# C30_Pocket_Console.net
KiCad netlist of a schematic drawn in EAGLE
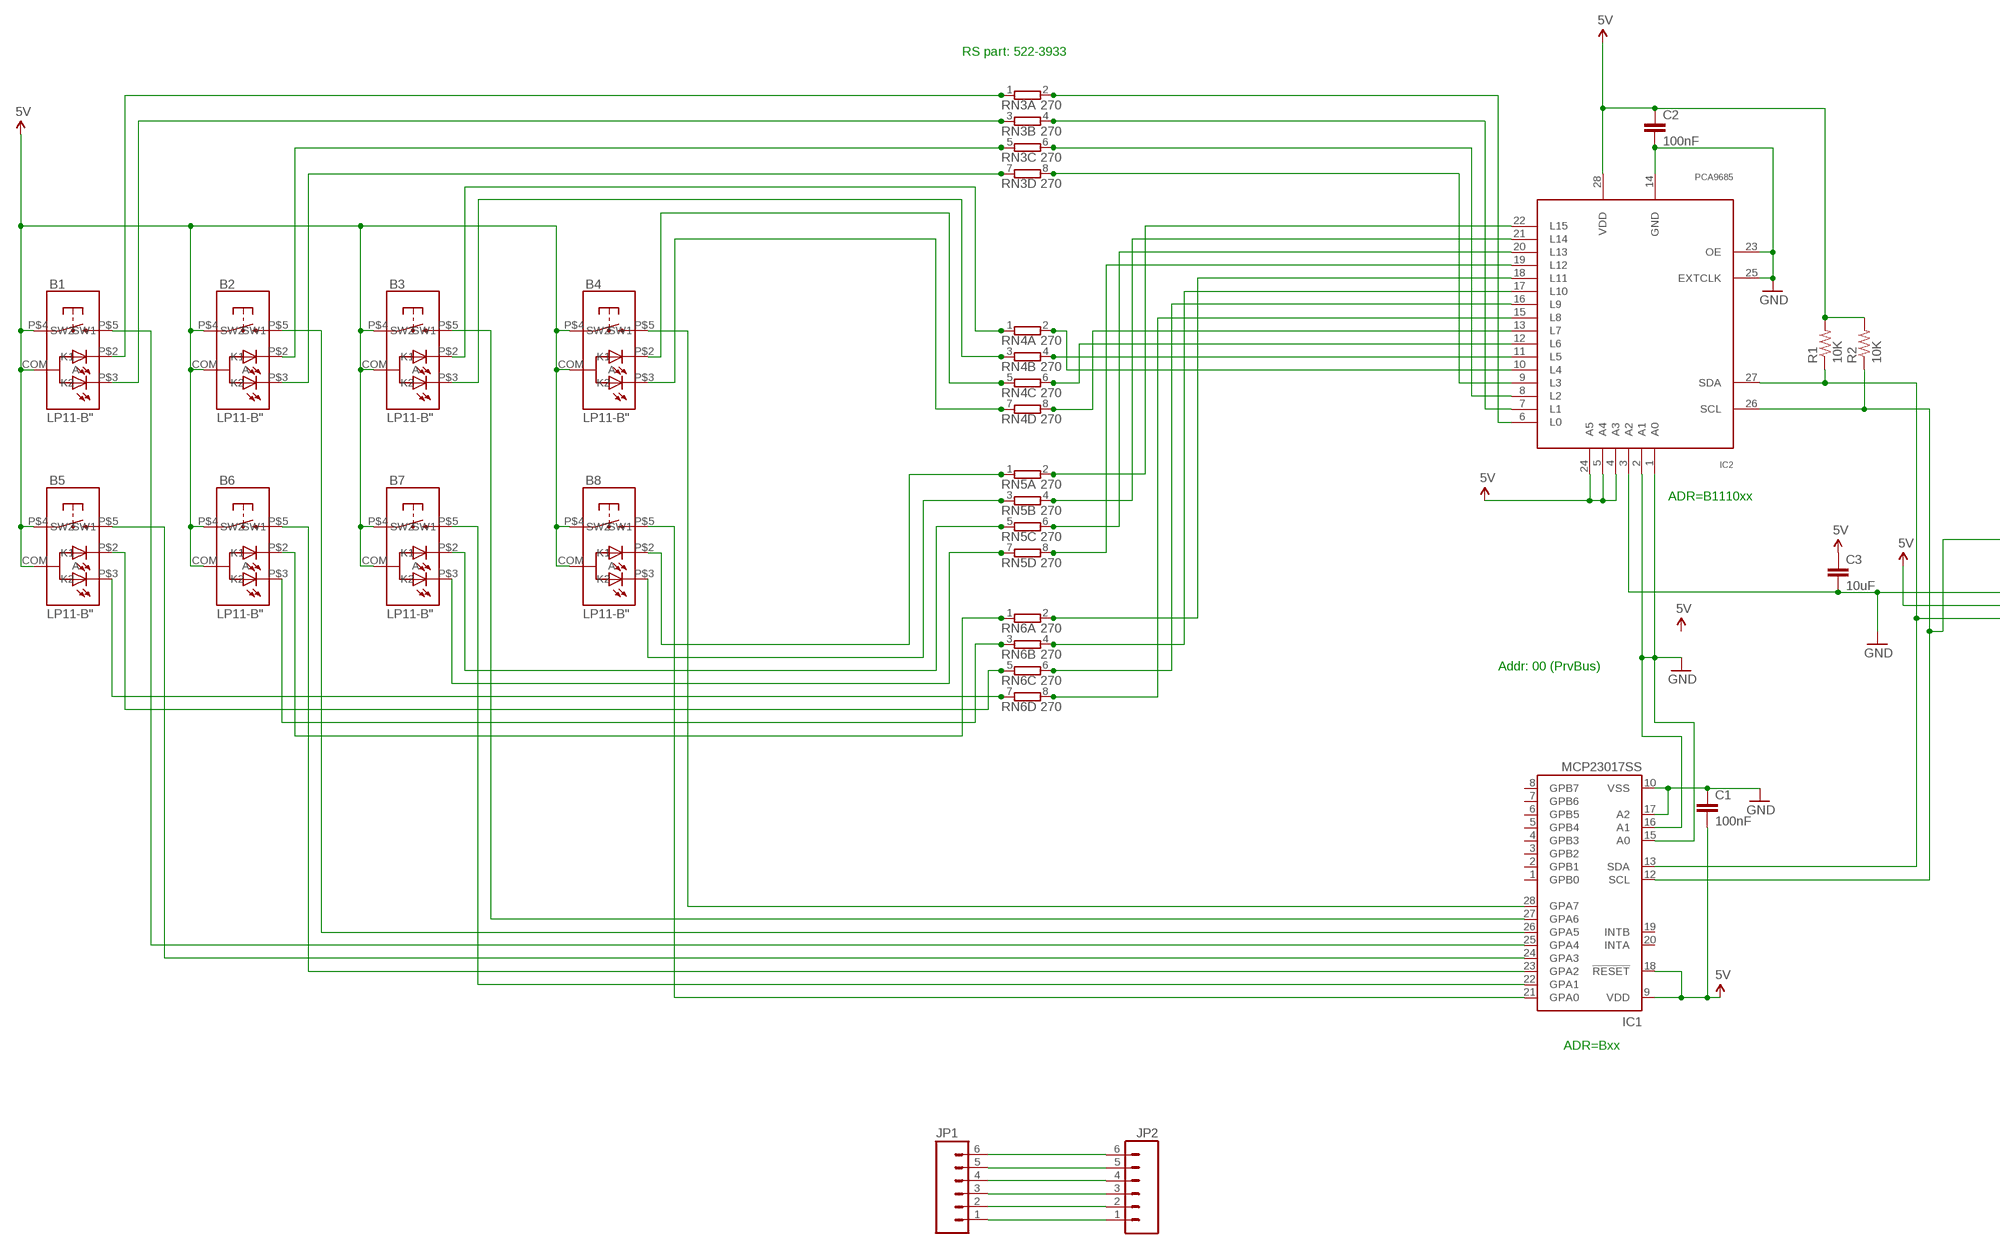
[diagram p0: schematic, sheet 1, part 1 of 2]
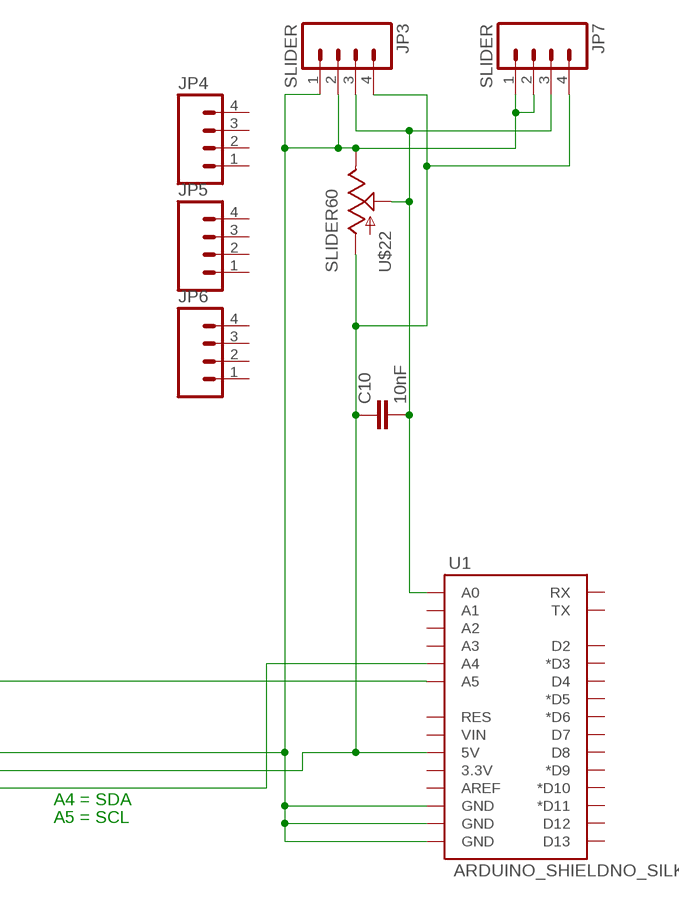
[diagram p1: schematic, sheet 1, part 2 of 2]

(export (version "E")
  (design (tool "Eeschema 10.0.6"))
  (components
    (comp (ref "B1")
      (value "LP11-B\"")
      (footprint "eagle-import:LP11")
      (libsource (lib "eagle-import") (part "LP11-B{dblquote}"))
    )
    (comp (ref "B2")
      (value "LP11-B\"")
      (footprint "eagle-import:LP11")
      (libsource (lib "eagle-import") (part "LP11-B{dblquote}"))
    )
    (comp (ref "B3")
      (value "LP11-B\"")
      (footprint "eagle-import:LP11")
      (libsource (lib "eagle-import") (part "LP11-B{dblquote}"))
    )
    (comp (ref "B4")
      (value "LP11-B\"")
      (footprint "eagle-import:LP11")
      (libsource (lib "eagle-import") (part "LP11-B{dblquote}"))
    )
    (comp (ref "B5")
      (value "LP11-B\"")
      (footprint "eagle-import:LP11")
      (libsource (lib "eagle-import") (part "LP11-B{dblquote}"))
    )
    (comp (ref "B6")
      (value "LP11-B\"")
      (footprint "eagle-import:LP11")
      (libsource (lib "eagle-import") (part "LP11-B{dblquote}"))
    )
    (comp (ref "B7")
      (value "LP11-B\"")
      (footprint "eagle-import:LP11")
      (libsource (lib "eagle-import") (part "LP11-B{dblquote}"))
    )
    (comp (ref "B8")
      (value "LP11-B\"")
      (footprint "eagle-import:LP11")
      (libsource (lib "eagle-import") (part "LP11-B{dblquote}"))
    )
    (comp (ref "C1")
      (value "100nF")
      (footprint "eagle-import:AXIAL-5MM")
      (libsource (lib "eagle-import") (part "CAP_"))
    )
    (comp (ref "C2")
      (value "100nF")
      (footprint "eagle-import:AXIAL-5MM")
      (libsource (lib "eagle-import") (part "CAP_"))
    )
    (comp (ref "C3")
      (value "10uF")
      (footprint "eagle-import:AXIAL-5MM")
      (libsource (lib "eagle-import") (part "CAP_"))
    )
    (comp (ref "C10")
      (value "10nF")
      (footprint "eagle-import:AXIAL-5MM")
      (libsource (lib "eagle-import") (part "CAP_"))
    )
    (comp (ref "IC1")
      (value "MCP23017SS")
      (footprint "eagle-import:SSOP28")
      (fields
        (field (name "MF") "MICROCHIP")
        (field (name "MPN") "MCP23017-E/SS")
        (field (name "MPN_1") "MCP23017-E/SS")
        (field (name "OC_FARNELL") "1467674")
        (field (name "OC_NEWARK") "31K2960")
      )
      (libsource (lib "eagle-import") (part "MCP23017SS"))
    )
    (comp (ref "IC2")
      (value "PCA9685")
      (footprint "eagle-import:TSSOP28")
      (libsource (lib "eagle-import") (part "PCA9685"))
    )
    (comp (ref "JP1")
      (value "M06POLAR")
      (footprint "eagle-import:MOLEX-1X6")
      (libsource (lib "eagle-import") (part "M06POLAR"))
    )
    (comp (ref "JP2")
      (value "M06POLAR")
      (footprint "eagle-import:MOLEX-1X6")
      (libsource (lib "eagle-import") (part "M06POLAR"))
    )
    (comp (ref "JP3")
      (value "SLIDER")
      (footprint "eagle-import:1X04")
      (libsource (lib "eagle-import") (part "M04PTH"))
    )
    (comp (ref "JP4")
      (value "M04PTH")
      (footprint "eagle-import:1X04")
      (libsource (lib "eagle-import") (part "M04PTH"))
    )
    (comp (ref "JP5")
      (value "M04PTH")
      (footprint "eagle-import:1X04")
      (libsource (lib "eagle-import") (part "M04PTH"))
    )
    (comp (ref "JP6")
      (value "M04PTH")
      (footprint "eagle-import:1X04")
      (libsource (lib "eagle-import") (part "M04PTH"))
    )
    (comp (ref "JP7")
      (value "SLIDER")
      (footprint "eagle-import:1X04")
      (libsource (lib "eagle-import") (part "M04PTH"))
    )
    (comp (ref "R1")
      (value "10K")
      (footprint "eagle-import:0603-RES")
      (libsource (lib "eagle-import") (part "RESISTOR0603-RES"))
    )
    (comp (ref "R2")
      (value "10K")
      (footprint "eagle-import:0603-RES")
      (libsource (lib "eagle-import") (part "RESISTOR0603-RES"))
    )
    (comp (ref "RN3")
      (value "270")
      (footprint "eagle-import:SIL8")
      (libsource (lib "eagle-import") (part "E4R"))
    )
    (comp (ref "RN4")
      (value "270")
      (footprint "eagle-import:SIL8")
      (libsource (lib "eagle-import") (part "E4R"))
    )
    (comp (ref "RN5")
      (value "270")
      (footprint "eagle-import:SIL8")
      (libsource (lib "eagle-import") (part "E4R"))
    )
    (comp (ref "RN6")
      (value "270")
      (footprint "eagle-import:SIL8")
      (libsource (lib "eagle-import") (part "E4R"))
    )
    (comp (ref "U$22")
      (value "SLIDER60")
      (footprint "eagle-import:SLIDER60")
      (libsource (lib "eagle-import") (part "SLIDER60"))
    )
    (comp (ref "U1")
      (value "ARDUINO_SHIELDNO_SILK")
      (footprint "eagle-import:DUEMILANOVE_VIAS")
      (libsource (lib "eagle-import") (part "ARDUINO_SHIELDNO_SILK"))
    )
  )
  (nets
    (net (code "1") (name "5V") (class "Default")
      (node (ref "B1") (pin "COM") (pinfunction "A_COM") (pintype "bidirectional"))
      (node (ref "B1") (pin "P$4") (pinfunction "SW1_P$4") (pintype "bidirectional"))
      (node (ref "B2") (pin "COM") (pinfunction "A_COM") (pintype "bidirectional"))
      (node (ref "B2") (pin "P$4") (pinfunction "SW1_P$4") (pintype "bidirectional"))
      (node (ref "B3") (pin "COM") (pinfunction "A_COM") (pintype "bidirectional"))
      (node (ref "B3") (pin "P$4") (pinfunction "SW1_P$4") (pintype "bidirectional"))
      (node (ref "B4") (pin "COM") (pinfunction "A_COM") (pintype "bidirectional"))
      (node (ref "B4") (pin "P$4") (pinfunction "SW1_P$4") (pintype "bidirectional"))
      (node (ref "B5") (pin "COM") (pinfunction "A_COM") (pintype "bidirectional"))
      (node (ref "B5") (pin "P$4") (pinfunction "SW1_P$4") (pintype "bidirectional"))
      (node (ref "B6") (pin "COM") (pinfunction "A_COM") (pintype "bidirectional"))
      (node (ref "B6") (pin "P$4") (pinfunction "SW1_P$4") (pintype "bidirectional"))
      (node (ref "B7") (pin "COM") (pinfunction "A_COM") (pintype "bidirectional"))
      (node (ref "B7") (pin "P$4") (pinfunction "SW1_P$4") (pintype "bidirectional"))
      (node (ref "B8") (pin "COM") (pinfunction "A_COM") (pintype "bidirectional"))
      (node (ref "B8") (pin "P$4") (pinfunction "SW1_P$4") (pintype "bidirectional"))
      (node (ref "C1") (pin "P$2") (pinfunction "2_P$2") (pintype "passive"))
      (node (ref "C10") (pin "P$1") (pinfunction "1_P$1") (pintype "passive"))
      (node (ref "C2") (pin "P$1") (pinfunction "1_P$1") (pintype "passive"))
      (node (ref "C3") (pin "P$1") (pinfunction "1_P$1") (pintype "passive"))
      (node (ref "IC1") (pin "18") (pinfunction "~{RESET}_18") (pintype "input"))
      (node (ref "IC1") (pin "9") (pinfunction "VDD_9") (pintype "power_in"))
      (node (ref "IC2") (pin "24") (pinfunction "A5_24") (pintype "input"))
      (node (ref "IC2") (pin "28") (pinfunction "VDD_28") (pintype "power_in"))
      (node (ref "IC2") (pin "4") (pinfunction "A3_4") (pintype "input"))
      (node (ref "IC2") (pin "5") (pinfunction "A4_5") (pintype "input"))
      (node (ref "JP3") (pin "4") (pinfunction "4_4") (pintype "passive"))
      (node (ref "JP7") (pin "4") (pinfunction "4_4") (pintype "passive"))
      (node (ref "R1") (pin "2") (pinfunction "2_2") (pintype "passive"))
      (node (ref "R2") (pin "2") (pinfunction "2_2") (pintype "passive"))
      (node (ref "U$22") (pin "3") (pinfunction "A_3") (pintype "passive"))
      (node (ref "U1") (pin "5V") (pinfunction "5V_5V") (pintype "bidirectional"))
    )
    (net (code "2") (name "GND") (class "Default")
      (node (ref "C1") (pin "P$1") (pinfunction "1_P$1") (pintype "passive"))
      (node (ref "C2") (pin "P$2") (pinfunction "2_P$2") (pintype "passive"))
      (node (ref "C3") (pin "P$2") (pinfunction "2_P$2") (pintype "passive"))
      (node (ref "IC1") (pin "10") (pinfunction "VSS_10") (pintype "power_in"))
      (node (ref "IC1") (pin "15") (pinfunction "A0_15") (pintype "input"))
      (node (ref "IC1") (pin "16") (pinfunction "A1_16") (pintype "input"))
      (node (ref "IC1") (pin "17") (pinfunction "A2_17") (pintype "input"))
      (node (ref "IC2") (pin "1") (pinfunction "A0_1") (pintype "input"))
      (node (ref "IC2") (pin "14") (pinfunction "GND_14") (pintype "power_in"))
      (node (ref "IC2") (pin "2") (pinfunction "A1_2") (pintype "input"))
      (node (ref "IC2") (pin "23") (pinfunction "OE_23") (pintype "input"))
      (node (ref "IC2") (pin "25") (pinfunction "EXTCLK_25") (pintype "input"))
      (node (ref "IC2") (pin "3") (pinfunction "A2_3") (pintype "input"))
      (node (ref "JP3") (pin "1") (pinfunction "1_1") (pintype "passive"))
      (node (ref "JP3") (pin "2") (pinfunction "2_2") (pintype "passive"))
      (node (ref "JP7") (pin "1") (pinfunction "1_1") (pintype "passive"))
      (node (ref "JP7") (pin "2") (pinfunction "2_2") (pintype "passive"))
      (node (ref "U$22") (pin "1") (pinfunction "E_1") (pintype "passive"))
      (node (ref "U1") (pin "GND@0") (pinfunction "GND_GND@0") (pintype "bidirectional"))
      (node (ref "U1") (pin "GND@1") (pinfunction "GND_GND@1") (pintype "bidirectional"))
      (node (ref "U1") (pin "GND@2") (pinfunction "GND_GND@2") (pintype "bidirectional"))
    )
    (net (code "3") (name "Net-(B1-K1)") (class "Default")
      (node (ref "B1") (pin "P$2") (pinfunction "K1_P$2") (pintype "bidirectional"))
      (node (ref "RN3") (pin "1") (pinfunction "1_1") (pintype "passive"))
    )
    (net (code "4") (name "Net-(B1-K2)") (class "Default")
      (node (ref "B1") (pin "P$3") (pinfunction "K2_P$3") (pintype "bidirectional"))
      (node (ref "RN3") (pin "3") (pinfunction "1_3") (pintype "passive"))
    )
    (net (code "5") (name "Net-(B1-SW2)") (class "Default")
      (node (ref "B1") (pin "P$5") (pinfunction "SW2_P$5") (pintype "bidirectional"))
      (node (ref "IC1") (pin "25") (pinfunction "GPA4_25") (pintype "bidirectional"))
    )
    (net (code "6") (name "Net-(B2-K1)") (class "Default")
      (node (ref "B2") (pin "P$2") (pinfunction "K1_P$2") (pintype "bidirectional"))
      (node (ref "RN3") (pin "5") (pinfunction "1_5") (pintype "passive"))
    )
    (net (code "7") (name "Net-(B2-K2)") (class "Default")
      (node (ref "B2") (pin "P$3") (pinfunction "K2_P$3") (pintype "bidirectional"))
      (node (ref "RN3") (pin "7") (pinfunction "1_7") (pintype "passive"))
    )
    (net (code "8") (name "Net-(B2-SW2)") (class "Default")
      (node (ref "B2") (pin "P$5") (pinfunction "SW2_P$5") (pintype "bidirectional"))
      (node (ref "IC1") (pin "26") (pinfunction "GPA5_26") (pintype "bidirectional"))
    )
    (net (code "9") (name "Net-(B3-K1)") (class "Default")
      (node (ref "B3") (pin "P$2") (pinfunction "K1_P$2") (pintype "bidirectional"))
      (node (ref "RN4") (pin "1") (pinfunction "1_1") (pintype "passive"))
    )
    (net (code "10") (name "Net-(B3-K2)") (class "Default")
      (node (ref "B3") (pin "P$3") (pinfunction "K2_P$3") (pintype "bidirectional"))
      (node (ref "RN4") (pin "3") (pinfunction "1_3") (pintype "passive"))
    )
    (net (code "11") (name "Net-(B3-SW2)") (class "Default")
      (node (ref "B3") (pin "P$5") (pinfunction "SW2_P$5") (pintype "bidirectional"))
      (node (ref "IC1") (pin "27") (pinfunction "GPA6_27") (pintype "bidirectional"))
    )
    (net (code "12") (name "Net-(B4-K1)") (class "Default")
      (node (ref "B4") (pin "P$2") (pinfunction "K1_P$2") (pintype "bidirectional"))
      (node (ref "RN4") (pin "5") (pinfunction "1_5") (pintype "passive"))
    )
    (net (code "13") (name "Net-(B4-K2)") (class "Default")
      (node (ref "B4") (pin "P$3") (pinfunction "K2_P$3") (pintype "bidirectional"))
      (node (ref "RN4") (pin "7") (pinfunction "1_7") (pintype "passive"))
    )
    (net (code "14") (name "Net-(B4-SW2)") (class "Default")
      (node (ref "B4") (pin "P$5") (pinfunction "SW2_P$5") (pintype "bidirectional"))
      (node (ref "IC1") (pin "28") (pinfunction "GPA7_28") (pintype "bidirectional"))
    )
    (net (code "15") (name "Net-(B5-K1)") (class "Default")
      (node (ref "B5") (pin "P$2") (pinfunction "K1_P$2") (pintype "bidirectional"))
      (node (ref "RN6") (pin "5") (pinfunction "1_5") (pintype "passive"))
    )
    (net (code "16") (name "Net-(B5-K2)") (class "Default")
      (node (ref "B5") (pin "P$3") (pinfunction "K2_P$3") (pintype "bidirectional"))
      (node (ref "RN6") (pin "7") (pinfunction "1_7") (pintype "passive"))
    )
    (net (code "17") (name "Net-(B5-SW2)") (class "Default")
      (node (ref "B5") (pin "P$5") (pinfunction "SW2_P$5") (pintype "bidirectional"))
      (node (ref "IC1") (pin "24") (pinfunction "GPA3_24") (pintype "bidirectional"))
    )
    (net (code "18") (name "Net-(B6-K1)") (class "Default")
      (node (ref "B6") (pin "P$2") (pinfunction "K1_P$2") (pintype "bidirectional"))
      (node (ref "RN6") (pin "1") (pinfunction "1_1") (pintype "passive"))
    )
    (net (code "19") (name "Net-(B6-K2)") (class "Default")
      (node (ref "B6") (pin "P$3") (pinfunction "K2_P$3") (pintype "bidirectional"))
      (node (ref "RN6") (pin "3") (pinfunction "1_3") (pintype "passive"))
    )
    (net (code "20") (name "Net-(B6-SW2)") (class "Default")
      (node (ref "B6") (pin "P$5") (pinfunction "SW2_P$5") (pintype "bidirectional"))
      (node (ref "IC1") (pin "23") (pinfunction "GPA2_23") (pintype "bidirectional"))
    )
    (net (code "21") (name "Net-(B7-K1)") (class "Default")
      (node (ref "B7") (pin "P$2") (pinfunction "K1_P$2") (pintype "bidirectional"))
      (node (ref "RN5") (pin "5") (pinfunction "1_5") (pintype "passive"))
    )
    (net (code "22") (name "Net-(B7-K2)") (class "Default")
      (node (ref "B7") (pin "P$3") (pinfunction "K2_P$3") (pintype "bidirectional"))
      (node (ref "RN5") (pin "7") (pinfunction "1_7") (pintype "passive"))
    )
    (net (code "23") (name "Net-(B7-SW2)") (class "Default")
      (node (ref "B7") (pin "P$5") (pinfunction "SW2_P$5") (pintype "bidirectional"))
      (node (ref "IC1") (pin "22") (pinfunction "GPA1_22") (pintype "bidirectional"))
    )
    (net (code "24") (name "Net-(B8-K1)") (class "Default")
      (node (ref "B8") (pin "P$2") (pinfunction "K1_P$2") (pintype "bidirectional"))
      (node (ref "RN5") (pin "1") (pinfunction "1_1") (pintype "passive"))
    )
    (net (code "25") (name "Net-(B8-K2)") (class "Default")
      (node (ref "B8") (pin "P$3") (pinfunction "K2_P$3") (pintype "bidirectional"))
      (node (ref "RN5") (pin "3") (pinfunction "1_3") (pintype "passive"))
    )
    (net (code "26") (name "Net-(B8-SW2)") (class "Default")
      (node (ref "B8") (pin "P$5") (pinfunction "SW2_P$5") (pintype "bidirectional"))
      (node (ref "IC1") (pin "21") (pinfunction "GPA0_21") (pintype "bidirectional"))
    )
    (net (code "27") (name "Net-(C10-2)") (class "Default")
      (node (ref "C10") (pin "P$2") (pinfunction "2_P$2") (pintype "passive"))
      (node (ref "JP3") (pin "3") (pinfunction "3_3") (pintype "passive"))
      (node (ref "JP7") (pin "3") (pinfunction "3_3") (pintype "passive"))
      (node (ref "U$22") (pin "2A") (pinfunction "S_2A") (pintype "passive"))
      (node (ref "U1") (pin "A0") (pinfunction "A0_A0") (pintype "bidirectional"))
    )
    (net (code "28") (name "Net-(IC1-SCL)") (class "Default")
      (node (ref "IC1") (pin "12") (pinfunction "SCL_12") (pintype "input"))
      (node (ref "IC2") (pin "26") (pinfunction "SCL_26") (pintype "input"))
      (node (ref "R2") (pin "1") (pinfunction "1_1") (pintype "passive"))
      (node (ref "U1") (pin "A5") (pinfunction "A5_A5") (pintype "bidirectional"))
    )
    (net (code "29") (name "Net-(IC1-SDA)") (class "Default")
      (node (ref "IC1") (pin "13") (pinfunction "SDA_13") (pintype "bidirectional"))
      (node (ref "IC2") (pin "27") (pinfunction "SDA_27") (pintype "input"))
      (node (ref "R1") (pin "1") (pinfunction "1_1") (pintype "passive"))
      (node (ref "U1") (pin "A4") (pinfunction "A4_A4") (pintype "bidirectional"))
    )
    (net (code "30") (name "Net-(IC2-L0)") (class "Default")
      (node (ref "IC2") (pin "6") (pinfunction "L0_6") (pintype "output"))
      (node (ref "RN3") (pin "2") (pinfunction "2_2") (pintype "passive"))
    )
    (net (code "31") (name "Net-(IC2-L1)") (class "Default")
      (node (ref "IC2") (pin "7") (pinfunction "L1_7") (pintype "output"))
      (node (ref "RN3") (pin "4") (pinfunction "2_4") (pintype "passive"))
    )
    (net (code "32") (name "Net-(IC2-L2)") (class "Default")
      (node (ref "IC2") (pin "8") (pinfunction "L2_8") (pintype "output"))
      (node (ref "RN3") (pin "6") (pinfunction "2_6") (pintype "passive"))
    )
    (net (code "33") (name "Net-(IC2-L3)") (class "Default")
      (node (ref "IC2") (pin "9") (pinfunction "L3_9") (pintype "output"))
      (node (ref "RN3") (pin "8") (pinfunction "2_8") (pintype "passive"))
    )
    (net (code "34") (name "Net-(IC2-L4)") (class "Default")
      (node (ref "IC2") (pin "10") (pinfunction "L4_10") (pintype "output"))
      (node (ref "RN4") (pin "2") (pinfunction "2_2") (pintype "passive"))
    )
    (net (code "35") (name "Net-(IC2-L5)") (class "Default")
      (node (ref "IC2") (pin "11") (pinfunction "L5_11") (pintype "output"))
      (node (ref "RN4") (pin "4") (pinfunction "2_4") (pintype "passive"))
    )
    (net (code "36") (name "Net-(IC2-L6)") (class "Default")
      (node (ref "IC2") (pin "12") (pinfunction "L6_12") (pintype "output"))
      (node (ref "RN4") (pin "6") (pinfunction "2_6") (pintype "passive"))
    )
    (net (code "37") (name "Net-(IC2-L7)") (class "Default")
      (node (ref "IC2") (pin "13") (pinfunction "L7_13") (pintype "output"))
      (node (ref "RN4") (pin "8") (pinfunction "2_8") (pintype "passive"))
    )
    (net (code "38") (name "Net-(IC2-L8)") (class "Default")
      (node (ref "IC2") (pin "15") (pinfunction "L8_15") (pintype "output"))
      (node (ref "RN6") (pin "8") (pinfunction "2_8") (pintype "passive"))
    )
    (net (code "39") (name "Net-(IC2-L9)") (class "Default")
      (node (ref "IC2") (pin "16") (pinfunction "L9_16") (pintype "output"))
      (node (ref "RN6") (pin "6") (pinfunction "2_6") (pintype "passive"))
    )
    (net (code "40") (name "Net-(IC2-L10)") (class "Default")
      (node (ref "IC2") (pin "17") (pinfunction "L10_17") (pintype "output"))
      (node (ref "RN6") (pin "4") (pinfunction "2_4") (pintype "passive"))
    )
    (net (code "41") (name "Net-(IC2-L11)") (class "Default")
      (node (ref "IC2") (pin "18") (pinfunction "L11_18") (pintype "output"))
      (node (ref "RN6") (pin "2") (pinfunction "2_2") (pintype "passive"))
    )
    (net (code "42") (name "Net-(IC2-L12)") (class "Default")
      (node (ref "IC2") (pin "19") (pinfunction "L12_19") (pintype "output"))
      (node (ref "RN5") (pin "8") (pinfunction "2_8") (pintype "passive"))
    )
    (net (code "43") (name "Net-(IC2-L13)") (class "Default")
      (node (ref "IC2") (pin "20") (pinfunction "L13_20") (pintype "output"))
      (node (ref "RN5") (pin "6") (pinfunction "2_6") (pintype "passive"))
    )
    (net (code "44") (name "Net-(IC2-L14)") (class "Default")
      (node (ref "IC2") (pin "21") (pinfunction "L14_21") (pintype "output"))
      (node (ref "RN5") (pin "4") (pinfunction "2_4") (pintype "passive"))
    )
    (net (code "45") (name "Net-(IC2-L15)") (class "Default")
      (node (ref "IC2") (pin "22") (pinfunction "L15_22") (pintype "output"))
      (node (ref "RN5") (pin "2") (pinfunction "2_2") (pintype "passive"))
    )
    (net (code "46") (name "Net-(JP1-Pad1)") (class "Default")
      (node (ref "JP1") (pin "1") (pinfunction "1_1") (pintype "passive"))
      (node (ref "JP2") (pin "1") (pinfunction "1_1") (pintype "passive"))
    )
    (net (code "47") (name "Net-(JP1-Pad2)") (class "Default")
      (node (ref "JP1") (pin "2") (pinfunction "2_2") (pintype "passive"))
      (node (ref "JP2") (pin "2") (pinfunction "2_2") (pintype "passive"))
    )
    (net (code "48") (name "Net-(JP1-Pad3)") (class "Default")
      (node (ref "JP1") (pin "3") (pinfunction "3_3") (pintype "passive"))
      (node (ref "JP2") (pin "3") (pinfunction "3_3") (pintype "passive"))
    )
    (net (code "49") (name "Net-(JP1-Pad4)") (class "Default")
      (node (ref "JP1") (pin "4") (pinfunction "4_4") (pintype "passive"))
      (node (ref "JP2") (pin "4") (pinfunction "4_4") (pintype "passive"))
    )
    (net (code "50") (name "Net-(JP1-Pad5)") (class "Default")
      (node (ref "JP1") (pin "5") (pinfunction "5_5") (pintype "passive"))
      (node (ref "JP2") (pin "5") (pinfunction "5_5") (pintype "passive"))
    )
    (net (code "51") (name "Net-(JP1-Pad6)") (class "Default")
      (node (ref "JP1") (pin "6") (pinfunction "6_6") (pintype "passive"))
      (node (ref "JP2") (pin "6") (pinfunction "6_6") (pintype "passive"))
    )
    (net (code "52") (name "unconnected-(IC1-GPB0-Pad1)") (class "Default")
      (node (ref "IC1") (pin "1") (pinfunction "GPB0_1") (pintype "bidirectional"))
    )
    (net (code "53") (name "unconnected-(IC1-GPB1-Pad2)") (class "Default")
      (node (ref "IC1") (pin "2") (pinfunction "GPB1_2") (pintype "bidirectional"))
    )
    (net (code "54") (name "unconnected-(IC1-GPB2-Pad3)") (class "Default")
      (node (ref "IC1") (pin "3") (pinfunction "GPB2_3") (pintype "bidirectional"))
    )
    (net (code "55") (name "unconnected-(IC1-GPB3-Pad4)") (class "Default")
      (node (ref "IC1") (pin "4") (pinfunction "GPB3_4") (pintype "bidirectional"))
    )
    (net (code "56") (name "unconnected-(IC1-GPB4-Pad5)") (class "Default")
      (node (ref "IC1") (pin "5") (pinfunction "GPB4_5") (pintype "bidirectional"))
    )
    (net (code "57") (name "unconnected-(IC1-GPB5-Pad6)") (class "Default")
      (node (ref "IC1") (pin "6") (pinfunction "GPB5_6") (pintype "bidirectional"))
    )
    (net (code "58") (name "unconnected-(IC1-GPB6-Pad7)") (class "Default")
      (node (ref "IC1") (pin "7") (pinfunction "GPB6_7") (pintype "bidirectional"))
    )
    (net (code "59") (name "unconnected-(IC1-GPB7-Pad8)") (class "Default")
      (node (ref "IC1") (pin "8") (pinfunction "GPB7_8") (pintype "bidirectional"))
    )
    (net (code "60") (name "unconnected-(IC1-INTA-Pad20)") (class "Default")
      (node (ref "IC1") (pin "20") (pinfunction "INTA_20") (pintype "output"))
    )
    (net (code "61") (name "unconnected-(IC1-INTB-Pad19)") (class "Default")
      (node (ref "IC1") (pin "19") (pinfunction "INTB_19") (pintype "output"))
    )
    (net (code "62") (name "unconnected-(JP4-Pad1)") (class "Default")
      (node (ref "JP4") (pin "1") (pinfunction "1_1") (pintype "passive"))
    )
    (net (code "63") (name "unconnected-(JP4-Pad2)") (class "Default")
      (node (ref "JP4") (pin "2") (pinfunction "2_2") (pintype "passive"))
    )
    (net (code "64") (name "unconnected-(JP4-Pad3)") (class "Default")
      (node (ref "JP4") (pin "3") (pinfunction "3_3") (pintype "passive"))
    )
    (net (code "65") (name "unconnected-(JP4-Pad4)") (class "Default")
      (node (ref "JP4") (pin "4") (pinfunction "4_4") (pintype "passive"))
    )
    (net (code "66") (name "unconnected-(JP5-Pad1)") (class "Default")
      (node (ref "JP5") (pin "1") (pinfunction "1_1") (pintype "passive"))
    )
    (net (code "67") (name "unconnected-(JP5-Pad2)") (class "Default")
      (node (ref "JP5") (pin "2") (pinfunction "2_2") (pintype "passive"))
    )
    (net (code "68") (name "unconnected-(JP5-Pad3)") (class "Default")
      (node (ref "JP5") (pin "3") (pinfunction "3_3") (pintype "passive"))
    )
    (net (code "69") (name "unconnected-(JP5-Pad4)") (class "Default")
      (node (ref "JP5") (pin "4") (pinfunction "4_4") (pintype "passive"))
    )
    (net (code "70") (name "unconnected-(JP6-Pad1)") (class "Default")
      (node (ref "JP6") (pin "1") (pinfunction "1_1") (pintype "passive"))
    )
    (net (code "71") (name "unconnected-(JP6-Pad2)") (class "Default")
      (node (ref "JP6") (pin "2") (pinfunction "2_2") (pintype "passive"))
    )
    (net (code "72") (name "unconnected-(JP6-Pad3)") (class "Default")
      (node (ref "JP6") (pin "3") (pinfunction "3_3") (pintype "passive"))
    )
    (net (code "73") (name "unconnected-(JP6-Pad4)") (class "Default")
      (node (ref "JP6") (pin "4") (pinfunction "4_4") (pintype "passive"))
    )
    (net (code "74") (name "unconnected-(U1-*D3-PadD3)") (class "Default")
      (node (ref "U1") (pin "D3") (pinfunction "*D3_D3") (pintype "bidirectional"))
    )
    (net (code "75") (name "unconnected-(U1-*D5-PadD5)") (class "Default")
      (node (ref "U1") (pin "D5") (pinfunction "*D5_D5") (pintype "bidirectional"))
    )
    (net (code "76") (name "unconnected-(U1-*D6-PadD6)") (class "Default")
      (node (ref "U1") (pin "D6") (pinfunction "*D6_D6") (pintype "bidirectional"))
    )
    (net (code "77") (name "unconnected-(U1-*D9-PadD9)") (class "Default")
      (node (ref "U1") (pin "D9") (pinfunction "*D9_D9") (pintype "bidirectional"))
    )
    (net (code "78") (name "unconnected-(U1-*D10-PadD10)") (class "Default")
      (node (ref "U1") (pin "D10") (pinfunction "*D10_D10") (pintype "bidirectional"))
    )
    (net (code "79") (name "unconnected-(U1-*D11-PadD11)") (class "Default")
      (node (ref "U1") (pin "D11") (pinfunction "*D11_D11") (pintype "bidirectional"))
    )
    (net (code "80") (name "unconnected-(U1-Pad3.3V)") (class "Default")
      (node (ref "U1") (pin "3.3V") (pinfunction "3.3V_3.3V") (pintype "bidirectional"))
    )
    (net (code "81") (name "unconnected-(U1-PadA1)") (class "Default")
      (node (ref "U1") (pin "A1") (pinfunction "A1_A1") (pintype "bidirectional"))
    )
    (net (code "82") (name "unconnected-(U1-PadA2)") (class "Default")
      (node (ref "U1") (pin "A2") (pinfunction "A2_A2") (pintype "bidirectional"))
    )
    (net (code "83") (name "unconnected-(U1-PadA3)") (class "Default")
      (node (ref "U1") (pin "A3") (pinfunction "A3_A3") (pintype "bidirectional"))
    )
    (net (code "84") (name "unconnected-(U1-PadAREF)") (class "Default")
      (node (ref "U1") (pin "AREF") (pinfunction "AREF_AREF") (pintype "bidirectional"))
    )
    (net (code "85") (name "unconnected-(U1-PadD2)") (class "Default")
      (node (ref "U1") (pin "D2") (pinfunction "D2_D2") (pintype "bidirectional"))
    )
    (net (code "86") (name "unconnected-(U1-PadD4)") (class "Default")
      (node (ref "U1") (pin "D4") (pinfunction "D4_D4") (pintype "bidirectional"))
    )
    (net (code "87") (name "unconnected-(U1-PadD7)") (class "Default")
      (node (ref "U1") (pin "D7") (pinfunction "D7_D7") (pintype "bidirectional"))
    )
    (net (code "88") (name "unconnected-(U1-PadD8)") (class "Default")
      (node (ref "U1") (pin "D8") (pinfunction "D8_D8") (pintype "bidirectional"))
    )
    (net (code "89") (name "unconnected-(U1-PadD12)") (class "Default")
      (node (ref "U1") (pin "D12") (pinfunction "D12_D12") (pintype "bidirectional"))
    )
    (net (code "90") (name "unconnected-(U1-PadD13)") (class "Default")
      (node (ref "U1") (pin "D13") (pinfunction "D13_D13") (pintype "bidirectional"))
    )
    (net (code "91") (name "unconnected-(U1-PadRES)") (class "Default")
      (node (ref "U1") (pin "RES") (pinfunction "RES_RES") (pintype "bidirectional"))
    )
    (net (code "92") (name "unconnected-(U1-PadRX)") (class "Default")
      (node (ref "U1") (pin "RX") (pinfunction "RX_RX") (pintype "bidirectional"))
    )
    (net (code "93") (name "unconnected-(U1-PadTX)") (class "Default")
      (node (ref "U1") (pin "TX") (pinfunction "TX_TX") (pintype "bidirectional"))
    )
    (net (code "94") (name "unconnected-(U1-PadVIN)") (class "Default")
      (node (ref "U1") (pin "VIN") (pinfunction "VIN_VIN") (pintype "bidirectional"))
    )
  )
)
